# Adapter_JLink_EDU.net
KiCad netlist of a schematic drawn in Altium Designer
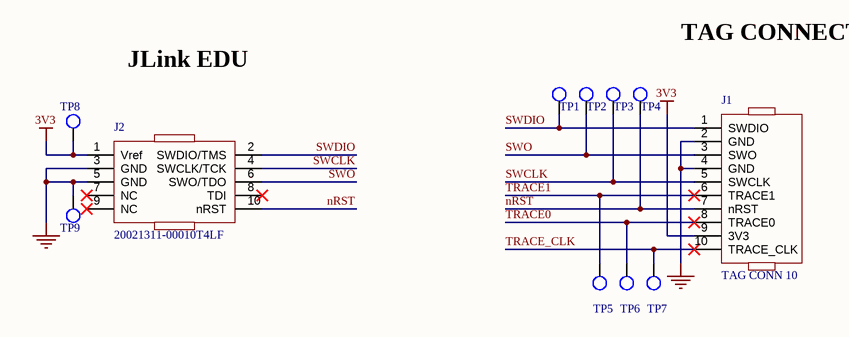
[diagram p0: Adapter_JLink_EDU.SchDoc]

(export (version "E")
  (design (tool "Eeschema 10.0.6"))
  (components
    (comp (ref "J1")
      (value "TAG CONN 10")
      (footprint "CONN HDR RECPT 20 2.54 TH TAG CONNECT 10")
      (description "Conn Shrouded Header HDR 10 POS 2.54mm Solder ST Thru-Hole")
      (fields
        (field (name "MANUFACTURER") "On-Shore Technology")
        (field (name "MANUFACTURER PART NUMBER") "302-S101")
      )
      (libsource (lib "Adapter_SchematicLib") (part "CONN HDR RECPT 10 2.54mm TH SWV"))
    )
    (comp (ref "J2")
      (value "20021311-00010T4LF")
      (footprint "CONN HDR PLUG 10 1.27mm JLink EDU")
      (description "Dual Row 10 Position 1.27 mm Board to Board Through Hole Female Socket Connector")
      (libsource (lib "Adapter_SchematicLib") (part "CONN HDR RECPT 10 1.27mm TH 20021311-00010T4LF"))
    )
    (comp (ref "TP1")
      (value "1mm")
      (footprint "TESTPOINT_SMT")
      (description "SMT testpoint")
      (libsource (lib "Adapter_SchematicLib") (part "TP 1mm"))
    )
    (comp (ref "TP2")
      (value "1mm")
      (footprint "TESTPOINT_SMT")
      (description "SMT testpoint")
      (libsource (lib "Adapter_SchematicLib") (part "TP 1mm"))
    )
    (comp (ref "TP3")
      (value "1mm")
      (footprint "TESTPOINT_SMT")
      (description "SMT testpoint")
      (libsource (lib "Adapter_SchematicLib") (part "TP 1mm"))
    )
    (comp (ref "TP4")
      (value "1mm")
      (footprint "TESTPOINT_SMT")
      (description "SMT testpoint")
      (libsource (lib "Adapter_SchematicLib") (part "TP 1mm"))
    )
    (comp (ref "TP5")
      (value "1mm")
      (footprint "TESTPOINT_SMT")
      (description "SMT testpoint")
      (libsource (lib "Adapter_SchematicLib") (part "TP 1mm"))
    )
    (comp (ref "TP6")
      (value "1mm")
      (footprint "TESTPOINT_SMT")
      (description "SMT testpoint")
      (libsource (lib "Adapter_SchematicLib") (part "TP 1mm"))
    )
    (comp (ref "TP7")
      (value "1mm")
      (footprint "TESTPOINT_SMT")
      (description "SMT testpoint")
      (libsource (lib "Adapter_SchematicLib") (part "TP 1mm"))
    )
    (comp (ref "TP8")
      (value "1mm")
      (footprint "TESTPOINT_SMT")
      (description "SMT testpoint")
      (libsource (lib "Adapter_SchematicLib") (part "TP 1mm"))
    )
    (comp (ref "TP9")
      (value "1mm")
      (footprint "TESTPOINT_SMT")
      (description "SMT testpoint")
      (libsource (lib "Adapter_SchematicLib") (part "TP 1mm"))
    )
  )
  (nets
    (net (code "1") (name "/SWCLK") (class "Default")
      (node (ref "J1") (pin "5") (pinfunction "SWCLK_5") (pintype "passive"))
      (node (ref "J2") (pin "4") (pinfunction "SWCLK/TCK_4") (pintype "passive"))
      (node (ref "TP3") (pin "1") (pinfunction "1_1") (pintype "passive"))
    )
    (net (code "2") (name "/SWDIO") (class "Default")
      (node (ref "J1") (pin "1") (pinfunction "SWDIO_1") (pintype "passive"))
      (node (ref "J2") (pin "2") (pinfunction "SWDIO/TMS_2") (pintype "passive"))
      (node (ref "TP1") (pin "1") (pinfunction "1_1") (pintype "passive"))
    )
    (net (code "3") (name "/SWO") (class "Default")
      (node (ref "J1") (pin "3") (pinfunction "SWO_3") (pintype "passive"))
      (node (ref "J2") (pin "6") (pinfunction "SWO/TDO_6") (pintype "passive"))
      (node (ref "TP2") (pin "1") (pinfunction "1_1") (pintype "passive"))
    )
    (net (code "4") (name "/TRACE0") (class "Default")
      (node (ref "J1") (pin "8") (pinfunction "TRACE0_8") (pintype "passive"))
      (node (ref "TP6") (pin "1") (pinfunction "1_1") (pintype "passive"))
    )
    (net (code "5") (name "/TRACE1") (class "Default")
      (node (ref "J1") (pin "6") (pinfunction "TRACE1_6") (pintype "passive"))
      (node (ref "TP5") (pin "1") (pinfunction "1_1") (pintype "passive"))
    )
    (net (code "6") (name "/TRACE_CLK") (class "Default")
      (node (ref "J1") (pin "10") (pinfunction "TRACE_CLK_10") (pintype "passive"))
      (node (ref "TP7") (pin "1") (pinfunction "1_1") (pintype "passive"))
    )
    (net (code "7") (name "/nRST") (class "Default")
      (node (ref "J1") (pin "7") (pinfunction "nRST_7") (pintype "passive"))
      (node (ref "J2") (pin "10") (pinfunction "nRST_10") (pintype "passive"))
      (node (ref "TP4") (pin "1") (pinfunction "1_1") (pintype "passive"))
    )
    (net (code "8") (name "3V3") (class "Default")
      (node (ref "J1") (pin "9") (pinfunction "3V3_9") (pintype "passive"))
      (node (ref "J2") (pin "1") (pinfunction "Vref_1") (pintype "passive"))
      (node (ref "TP8") (pin "1") (pinfunction "1_1") (pintype "passive"))
    )
    (net (code "9") (name "GND") (class "Default")
      (node (ref "J1") (pin "2") (pinfunction "GND_2") (pintype "passive"))
      (node (ref "J1") (pin "4") (pinfunction "GND_4") (pintype "passive"))
      (node (ref "J2") (pin "3") (pinfunction "GND_3") (pintype "passive"))
      (node (ref "J2") (pin "5") (pinfunction "GND_5") (pintype "passive"))
      (node (ref "TP9") (pin "1") (pinfunction "1_1") (pintype "passive"))
    )
    (net (code "10") (name "unconnected-(J2-NC-Pad7)") (class "Default")
      (node (ref "J2") (pin "7") (pinfunction "NC_7") (pintype "passive+no_connect"))
    )
    (net (code "11") (name "unconnected-(J2-NC-Pad9)") (class "Default")
      (node (ref "J2") (pin "9") (pinfunction "NC_9") (pintype "passive+no_connect"))
    )
    (net (code "12") (name "unconnected-(J2-TDI-Pad8)") (class "Default")
      (node (ref "J2") (pin "8") (pinfunction "TDI_8") (pintype "passive+no_connect"))
    )
  )
)
